# DA2_SCH_PAGE1.net
KiCad netlist of a schematic drawn in Altium Designer
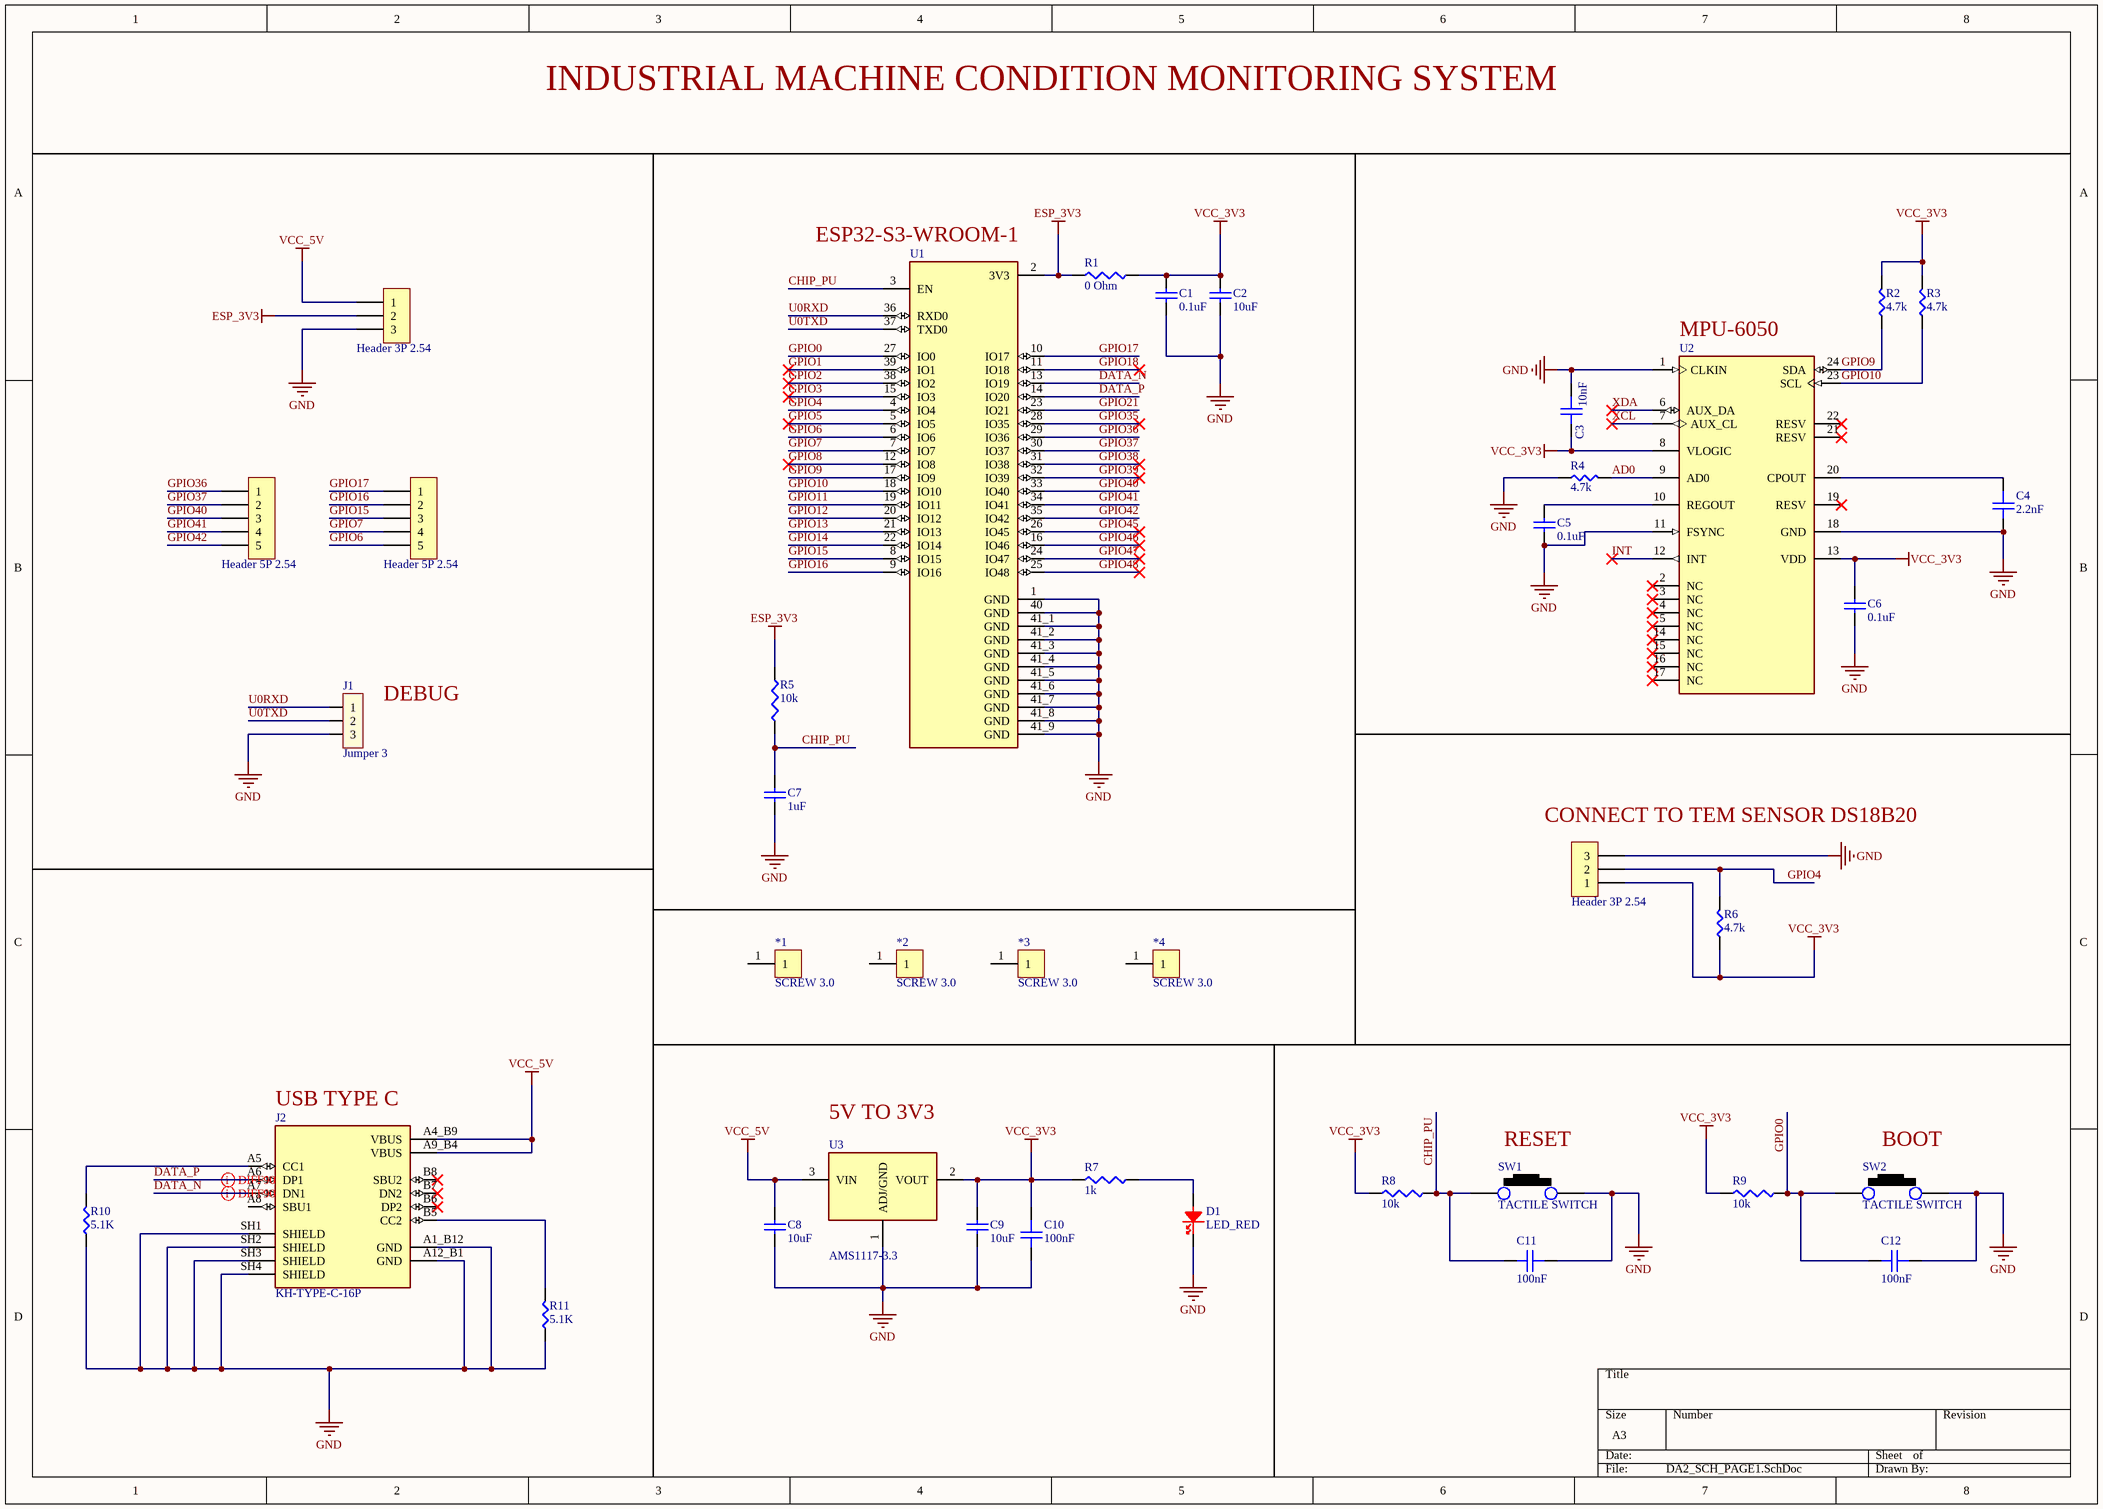
[diagram p0: DA2_SCH_PAGE1.SchDoc]

(export (version "E")
  (design (tool "Eeschema 10.0.6"))
  (components
    (comp (ref "*1")
      (value "SCREW 3.0")
      (footprint "Screw 3.0 v2")
      (libsource (lib "DA2") (part "SCREW 3.0"))
    )
    (comp (ref "*2")
      (value "SCREW 3.0")
      (footprint "Screw 3.0 v2")
      (libsource (lib "DA2") (part "SCREW 3.0"))
    )
    (comp (ref "*3")
      (value "SCREW 3.0")
      (footprint "Screw 3.0 v2")
      (libsource (lib "DA2") (part "SCREW 3.0"))
    )
    (comp (ref "*4")
      (value "SCREW 3.0")
      (footprint "Screw 3.0 v2")
      (libsource (lib "DA2") (part "SCREW 3.0"))
    )
    (comp (ref "C1")
      (value "0.1uF")
      (footprint "Tu 0805")
      (description "Dán 0805")
      (fields
        (field (name "MANUFACTURER") "Samsung Electro-Mechanics")
        (field (name "MANUFACTURER PART NUMBER") "CL05B104KB5NNWC")
      )
      (libsource (lib "DA2") (part "Tu 0.1uF"))
    )
    (comp (ref "C2")
      (value "10uF")
      (footprint "Tu 0805")
      (description "Dán 0805")
      (fields
        (field (name "MANUFACTURER") "Samsung Electro-Mechanics")
        (field (name "MANUFACTURER PART NUMBER") "CL05A106MP5NUNC")
      )
      (libsource (lib "DA2") (part "Tu 10uF"))
    )
    (comp (ref "C3")
      (value "10nF")
      (footprint "tu 0805")
      (description "Dán 0805")
      (libsource (lib "DA2") (part "Tu 10nF"))
    )
    (comp (ref "C4")
      (value "2.2nF")
      (footprint "tu 0805")
      (description "Dán 0805")
      (libsource (lib "DA2") (part "Tu 2.2nF"))
    )
    (comp (ref "C5")
      (value "0.1uF")
      (footprint "Tu 0805")
      (description "Dán 0805")
      (fields
        (field (name "MANUFACTURER") "Samsung Electro-Mechanics")
        (field (name "MANUFACTURER PART NUMBER") "CL05B104KB5NNWC")
      )
      (libsource (lib "DA2") (part "Tu 0.1uF"))
    )
    (comp (ref "C6")
      (value "0.1uF")
      (footprint "Tu 0805")
      (description "Dán 0805")
      (fields
        (field (name "MANUFACTURER") "Samsung Electro-Mechanics")
        (field (name "MANUFACTURER PART NUMBER") "CL05B104KB5NNWC")
      )
      (libsource (lib "DA2") (part "Tu 0.1uF"))
    )
    (comp (ref "C7")
      (value "1uF")
      (footprint "Tu 0805")
      (description "Dán 0805")
      (fields
        (field (name "MANUFACTURER") "Murata")
        (field (name "MANUFACTURER PART NUMBER") "GRM155R6YA105KE11D")
      )
      (libsource (lib "DA2") (part "Tu 1uF"))
    )
    (comp (ref "C8")
      (value "10uF")
      (footprint "Tu 0805")
      (description "Dán 0805")
      (fields
        (field (name "MANUFACTURER") "Samsung Electro-Mechanics")
        (field (name "MANUFACTURER PART NUMBER") "CL05A106MP5NUNC")
      )
      (libsource (lib "DA2") (part "Tu 10uF"))
    )
    (comp (ref "C9")
      (value "10uF")
      (footprint "Tu 0805")
      (description "Dán 0805")
      (fields
        (field (name "MANUFACTURER") "Samsung Electro-Mechanics")
        (field (name "MANUFACTURER PART NUMBER") "CL05A106MP5NUNC")
      )
      (libsource (lib "DA2") (part "Tu 10uF"))
    )
    (comp (ref "C10")
      (value "100nF")
      (footprint "tu 0805")
      (description "Dán 0805")
      (libsource (lib "DA2") (part "Tu 100nF"))
    )
    (comp (ref "C11")
      (value "100nF")
      (footprint "tu 0805")
      (description "Dán 0805")
      (libsource (lib "DA2") (part "Tu 100nF"))
    )
    (comp (ref "C12")
      (value "100nF")
      (footprint "tu 0805")
      (description "Dán 0805")
      (libsource (lib "DA2") (part "Tu 100nF"))
    )
    (comp (ref "D1")
      (value "LED_RED")
      (footprint "LED 0805")
      (description "LED RED 0402 SMD")
      (fields
        (field (name "MANUFACTURER") "Vishay")
        (field (name "MANUFACTURER PART NUMBER") "VLMS1500-GS08")
      )
      (libsource (lib "DA2") (part "VLMS1500-GS08"))
    )
    (comp (ref "H1")
      (value "Header 3P 2.54")
      (footprint "XH2.54M-3")
      (description "Cắm")
      (libsource (lib "DA2") (part "Header 3P 2.54 Duc Thang"))
    )
    (comp (ref "H2")
      (value "Header 5P 2.54")
      (footprint "XH2.54M-5")
      (description "Cắm")
      (libsource (lib "DA2") (part "Header 5P 2.54 Duc Thang"))
    )
    (comp (ref "H3")
      (value "Header 5P 2.54")
      (footprint "XH2.54M-5")
      (description "Cắm")
      (libsource (lib "DA2") (part "Header 5P 2.54 Duc Thang"))
    )
    (comp (ref "H4")
      (value "Header 3P 2.54")
      (footprint "XH2.54M-3")
      (description "Cắm")
      (libsource (lib "") (part "Header 3P 2.54 Duc Thang_1"))
    )
    (comp (ref "J1") (value "Jumper 3") (footprint "JP3") (libsource (lib "lpson") (part "JP3")))
    (comp (ref "J2")
      (value "KH-TYPE-C-16P")
      (footprint "KINGHELM_KH-TYPE-C-16P")
      (fields (field (name "MF") "kinghelm"))
      (libsource (lib "DA2") (part "KH-TYPE-C-16P"))
    )
    (comp (ref "R1")
      (value "0 Ohm")
      (footprint "Tro SMD 0805")
      (description "Dán 0805")
      (fields
        (field (name "MANUFACTURER") "Yageo Group")
        (field (name "MANUFACTURER PART NUMBER") "RC0402JR-070RL")
      )
      (libsource (lib "DA2") (part "Tro 0Ohm"))
    )
    (comp (ref "R2")
      (value "4.7k")
      (footprint "tro smd 0805")
      (description "Dán 0805")
      (libsource (lib "DA2") (part "Tro 4.7k"))
    )
    (comp (ref "R3")
      (value "4.7k")
      (footprint "tro smd 0805")
      (description "Dán 0805")
      (libsource (lib "DA2") (part "Tro 4.7k"))
    )
    (comp (ref "R4")
      (value "4.7k")
      (footprint "tro smd 0805")
      (description "Dán 0805")
      (libsource (lib "DA2") (part "Tro 4.7k"))
    )
    (comp (ref "R5")
      (value "10k")
      (footprint "Tro SMD 0805")
      (description "Dán 0805")
      (fields
        (field (name "MANUFACTURER") "Yageo Group")
        (field (name "MANUFACTURER PART NUMBER") "RC0402FR-0710KL")
      )
      (libsource (lib "DA2") (part "Tro 10k"))
    )
    (comp (ref "R6")
      (value "4.7k")
      (footprint "tro smd 0805")
      (description "Dán 0805")
      (libsource (lib "DA2") (part "Tro 4.7k"))
    )
    (comp (ref "R7")
      (value "1k")
      (footprint "Tro SMD 0805")
      (description "Dán 0805")
      (fields
        (field (name "MANUFACTURER") "Yageo Group")
        (field (name "MANUFACTURER PART NUMBER") "RC0402JR-071KL")
      )
      (libsource (lib "DA2") (part "Tro 1k"))
    )
    (comp (ref "R8")
      (value "10k")
      (footprint "Tro SMD 0805")
      (description "Dán 0805")
      (fields
        (field (name "MANUFACTURER") "Yageo Group")
        (field (name "MANUFACTURER PART NUMBER") "RC0402FR-0710KL")
      )
      (libsource (lib "DA2") (part "Tro 10k"))
    )
    (comp (ref "R9")
      (value "10k")
      (footprint "Tro SMD 0805")
      (description "Dán 0805")
      (fields
        (field (name "MANUFACTURER") "Yageo Group")
        (field (name "MANUFACTURER PART NUMBER") "RC0402FR-0710KL")
      )
      (libsource (lib "DA2") (part "Tro 10k"))
    )
    (comp (ref "R10")
      (value "5.1K")
      (footprint "tro smd 0805")
      (description "Dán 0805")
      (libsource (lib "DA2") (part "Tro 5.1K"))
    )
    (comp (ref "R11")
      (value "5.1K")
      (footprint "tro smd 0805")
      (description "Dán 0805")
      (libsource (lib "DA2") (part "Tro 5.1K"))
    )
    (comp (ref "SW1")
      (value "TACTILE SWITCH")
      (footprint "SWITCH SMD")
      (description "Tactile Switch SPST-NO Top Actuated Surface Mount")
      (fields
        (field (name "MANUFACTURER") "ITT C&K")
        (field (name "MANUFACTURER PART NUMBER") "RS-282G05A3-SMRT")
      )
      (libsource (lib "DA2") (part "SW1_RS-282G05A3-SMRT-SMD"))
    )
    (comp (ref "SW2")
      (value "TACTILE SWITCH")
      (footprint "SWITCH SMD")
      (description "Tactile Switch SPST-NO Top Actuated Surface Mount")
      (fields
        (field (name "MANUFACTURER") "ITT C&K")
        (field (name "MANUFACTURER PART NUMBER") "RS-282G05A3-SMRT")
      )
      (libsource (lib "DA2") (part "SW1_RS-282G05A3-SMRT-SMD"))
    )
    (comp (ref "U1")
      (value "ESP32-S3-WROOM-1-N8R2")
      (footprint "XCVR_ESP32-S3-WROOM-1-N8R2")
      (description "WiFi 802.11a/b/g/n, Bluetooth v5.0 Transceiver Module 2.4GHz Antenna Not Included -")
      (fields (field (name "MF") "Espressif Systems"))
      (libsource (lib "Schlib1") (part "ESP32-S3-WROOM-1-N8R2"))
    )
    (comp (ref "U2")
      (value "MPU-6050")
      (footprint "QFN50P400X400X95-24N")
      (description "MPU-6050 series Accelerometer, Gyroscope, 3 Axis Sensor Evaluation Board")
      (fields (field (name "MF") "TDK InvenSense"))
      (libsource (lib "Schlib1") (part "MPU-6050"))
    )
    (comp (ref "U3")
      (value "AMS1117-3.3")
      (footprint "SOT229P700X180-4N")
      (description "Linear Voltage Regulator IC Positive Fixed 1 Output 1A SOT-223-3L")
      (fields (field (name "MF") "UMW"))
      (libsource (lib "Schlib1") (part "AMS1117-3.3"))
    )
  )
  (nets
    (net (code "1") (name "/AD0") (class "Default")
      (node (ref "R4") (pin "2") (pinfunction "2_2") (pintype "passive"))
      (node (ref "U2") (pin "9") (pinfunction "AD0_9") (pintype "passive"))
    )
    (net (code "2") (name "/CHIP_PU") (class "Default")
      (node (ref "C11") (pin "2") (pinfunction "2_2") (pintype "passive"))
      (node (ref "C7") (pin "2") (pinfunction "2_2") (pintype "passive"))
      (node (ref "R5") (pin "1") (pinfunction "1_1") (pintype "passive"))
      (node (ref "R8") (pin "2") (pinfunction "2_2") (pintype "passive"))
      (node (ref "SW1") (pin "1") (pinfunction "1_1") (pintype "passive"))
      (node (ref "U1") (pin "3") (pinfunction "EN_3") (pintype "passive"))
    )
    (net (code "3") (name "/DATA_N") (class "Default")
      (node (ref "J2") (pin "A7") (pinfunction "DN1_A7") (pintype "bidirectional"))
      (node (ref "U1") (pin "13") (pinfunction "IO19_13") (pintype "bidirectional"))
    )
    (net (code "4") (name "/DATA_P") (class "Default")
      (node (ref "J2") (pin "A6") (pinfunction "DP1_A6") (pintype "bidirectional"))
      (node (ref "U1") (pin "14") (pinfunction "IO20_14") (pintype "bidirectional"))
    )
    (net (code "5") (name "/GPIO0") (class "Default")
      (node (ref "C12") (pin "2") (pinfunction "2_2") (pintype "passive"))
      (node (ref "R9") (pin "2") (pinfunction "2_2") (pintype "passive"))
      (node (ref "SW2") (pin "1") (pinfunction "1_1") (pintype "passive"))
      (node (ref "U1") (pin "27") (pinfunction "IO0_27") (pintype "bidirectional"))
    )
    (net (code "6") (name "/GPIO1") (class "Default")
      (node (ref "U1") (pin "39") (pinfunction "IO1_39") (pintype "bidirectional+no_connect"))
    )
    (net (code "7") (name "/GPIO2") (class "Default")
      (node (ref "U1") (pin "38") (pinfunction "IO2_38") (pintype "bidirectional+no_connect"))
    )
    (net (code "8") (name "/GPIO3") (class "Default")
      (node (ref "U1") (pin "15") (pinfunction "IO3_15") (pintype "bidirectional+no_connect"))
    )
    (net (code "9") (name "/GPIO4") (class "Default")
      (node (ref "H4") (pin "2") (pinfunction "2_2") (pintype "passive"))
      (node (ref "R6") (pin "2") (pinfunction "2_2") (pintype "passive"))
      (node (ref "U1") (pin "4") (pinfunction "IO4_4") (pintype "bidirectional"))
    )
    (net (code "10") (name "/GPIO5") (class "Default")
      (node (ref "U1") (pin "5") (pinfunction "IO5_5") (pintype "bidirectional+no_connect"))
    )
    (net (code "11") (name "/GPIO6") (class "Default")
      (node (ref "H3") (pin "5") (pinfunction "5_5") (pintype "passive"))
      (node (ref "U1") (pin "6") (pinfunction "IO6_6") (pintype "bidirectional"))
    )
    (net (code "12") (name "/GPIO7") (class "Default")
      (node (ref "H3") (pin "4") (pinfunction "4_4") (pintype "passive"))
      (node (ref "U1") (pin "7") (pinfunction "IO7_7") (pintype "bidirectional"))
    )
    (net (code "13") (name "/GPIO8") (class "Default")
      (node (ref "U1") (pin "12") (pinfunction "IO8_12") (pintype "bidirectional+no_connect"))
    )
    (net (code "14") (name "/GPIO9") (class "Default")
      (node (ref "R2") (pin "1") (pinfunction "1_1") (pintype "passive"))
      (node (ref "U1") (pin "17") (pinfunction "IO9_17") (pintype "bidirectional"))
      (node (ref "U2") (pin "24") (pinfunction "SDA_24") (pintype "bidirectional"))
    )
    (net (code "15") (name "/GPIO10") (class "Default")
      (node (ref "R3") (pin "1") (pinfunction "1_1") (pintype "passive"))
      (node (ref "U1") (pin "18") (pinfunction "IO10_18") (pintype "bidirectional"))
      (node (ref "U2") (pin "23") (pinfunction "SCL_23") (pintype "input"))
    )
    (net (code "16") (name "/GPIO11") (class "Default")
      (node (ref "U1") (pin "19") (pinfunction "IO11_19") (pintype "bidirectional"))
    )
    (net (code "17") (name "/GPIO12") (class "Default")
      (node (ref "U1") (pin "20") (pinfunction "IO12_20") (pintype "bidirectional"))
    )
    (net (code "18") (name "/GPIO13") (class "Default")
      (node (ref "U1") (pin "21") (pinfunction "IO13_21") (pintype "bidirectional"))
    )
    (net (code "19") (name "/GPIO14") (class "Default")
      (node (ref "U1") (pin "22") (pinfunction "IO14_22") (pintype "bidirectional"))
    )
    (net (code "20") (name "/GPIO15") (class "Default")
      (node (ref "H3") (pin "3") (pinfunction "3_3") (pintype "passive"))
      (node (ref "U1") (pin "8") (pinfunction "IO15_8") (pintype "bidirectional"))
    )
    (net (code "21") (name "/GPIO16") (class "Default")
      (node (ref "H3") (pin "2") (pinfunction "2_2") (pintype "passive"))
      (node (ref "U1") (pin "9") (pinfunction "IO16_9") (pintype "bidirectional"))
    )
    (net (code "22") (name "/GPIO17") (class "Default")
      (node (ref "H3") (pin "1") (pinfunction "1_1") (pintype "passive"))
      (node (ref "U1") (pin "10") (pinfunction "IO17_10") (pintype "bidirectional"))
    )
    (net (code "23") (name "/GPIO18") (class "Default")
      (node (ref "U1") (pin "11") (pinfunction "IO18_11") (pintype "bidirectional+no_connect"))
    )
    (net (code "24") (name "/GPIO21") (class "Default")
      (node (ref "U1") (pin "23") (pinfunction "IO21_23") (pintype "bidirectional"))
    )
    (net (code "25") (name "/GPIO35") (class "Default")
      (node (ref "U1") (pin "28") (pinfunction "IO35_28") (pintype "bidirectional+no_connect"))
    )
    (net (code "26") (name "/GPIO36") (class "Default")
      (node (ref "H2") (pin "1") (pinfunction "1_1") (pintype "passive"))
      (node (ref "U1") (pin "29") (pinfunction "IO36_29") (pintype "bidirectional"))
    )
    (net (code "27") (name "/GPIO37") (class "Default")
      (node (ref "H2") (pin "2") (pinfunction "2_2") (pintype "passive"))
      (node (ref "U1") (pin "30") (pinfunction "IO37_30") (pintype "bidirectional"))
    )
    (net (code "28") (name "/GPIO38") (class "Default")
      (node (ref "U1") (pin "31") (pinfunction "IO38_31") (pintype "bidirectional+no_connect"))
    )
    (net (code "29") (name "/GPIO39") (class "Default")
      (node (ref "U1") (pin "32") (pinfunction "IO39_32") (pintype "bidirectional+no_connect"))
    )
    (net (code "30") (name "/GPIO40") (class "Default")
      (node (ref "H2") (pin "3") (pinfunction "3_3") (pintype "passive"))
      (node (ref "U1") (pin "33") (pinfunction "IO40_33") (pintype "bidirectional"))
    )
    (net (code "31") (name "/GPIO41") (class "Default")
      (node (ref "H2") (pin "4") (pinfunction "4_4") (pintype "passive"))
      (node (ref "U1") (pin "34") (pinfunction "IO41_34") (pintype "bidirectional"))
    )
    (net (code "32") (name "/GPIO42") (class "Default")
      (node (ref "H2") (pin "5") (pinfunction "5_5") (pintype "passive"))
      (node (ref "U1") (pin "35") (pinfunction "IO42_35") (pintype "bidirectional"))
    )
    (net (code "33") (name "/GPIO45") (class "Default")
      (node (ref "U1") (pin "26") (pinfunction "IO45_26") (pintype "bidirectional+no_connect"))
    )
    (net (code "34") (name "/GPIO46") (class "Default")
      (node (ref "U1") (pin "16") (pinfunction "IO46_16") (pintype "bidirectional+no_connect"))
    )
    (net (code "35") (name "/GPIO47") (class "Default")
      (node (ref "U1") (pin "24") (pinfunction "IO47_24") (pintype "bidirectional+no_connect"))
    )
    (net (code "36") (name "/GPIO48") (class "Default")
      (node (ref "U1") (pin "25") (pinfunction "IO48_25") (pintype "bidirectional+no_connect"))
    )
    (net (code "37") (name "/INT") (class "Default")
      (node (ref "U2") (pin "12") (pinfunction "INT_12") (pintype "output+no_connect"))
    )
    (net (code "38") (name "/U0RXD") (class "Default")
      (node (ref "J1") (pin "1") (pinfunction "1_1") (pintype "passive"))
      (node (ref "U1") (pin "36") (pinfunction "RXD0_36") (pintype "bidirectional"))
    )
    (net (code "39") (name "/U0TXD") (class "Default")
      (node (ref "J1") (pin "2") (pinfunction "2_2") (pintype "passive"))
      (node (ref "U1") (pin "37") (pinfunction "TXD0_37") (pintype "bidirectional"))
    )
    (net (code "40") (name "/XCL") (class "Default")
      (node (ref "U2") (pin "7") (pinfunction "AUX_CL_7") (pintype "output+no_connect"))
    )
    (net (code "41") (name "/XDA") (class "Default")
      (node (ref "U2") (pin "6") (pinfunction "AUX_DA_6") (pintype "bidirectional+no_connect"))
    )
    (net (code "42") (name "ESP_3V3") (class "Default")
      (node (ref "H1") (pin "2") (pinfunction "2_2") (pintype "passive"))
      (node (ref "R1") (pin "1") (pinfunction "1_1") (pintype "passive"))
      (node (ref "R5") (pin "2") (pinfunction "2_2") (pintype "passive"))
      (node (ref "U1") (pin "2") (pinfunction "3V3_2") (pintype "power_in"))
    )
    (net (code "43") (name "GND") (class "Default")
      (node (ref "C1") (pin "1") (pinfunction "1_1") (pintype "passive"))
      (node (ref "C10") (pin "2") (pinfunction "2_2") (pintype "passive"))
      (node (ref "C11") (pin "1") (pinfunction "1_1") (pintype "passive"))
      (node (ref "C12") (pin "1") (pinfunction "1_1") (pintype "passive"))
      (node (ref "C2") (pin "1") (pinfunction "1_1") (pintype "passive"))
      (node (ref "C3") (pin "1") (pinfunction "1_1") (pintype "passive"))
      (node (ref "C4") (pin "2") (pinfunction "2_2") (pintype "passive"))
      (node (ref "C5") (pin "1") (pinfunction "1_1") (pintype "passive"))
      (node (ref "C6") (pin "1") (pinfunction "1_1") (pintype "passive"))
      (node (ref "C7") (pin "1") (pinfunction "1_1") (pintype "passive"))
      (node (ref "C8") (pin "1") (pinfunction "1_1") (pintype "passive"))
      (node (ref "C9") (pin "1") (pinfunction "1_1") (pintype "passive"))
      (node (ref "D1") (pin "1") (pinfunction "1_1") (pintype "passive"))
      (node (ref "H1") (pin "3") (pinfunction "3_3") (pintype "passive"))
      (node (ref "H4") (pin "3") (pinfunction "3_3") (pintype "passive"))
      (node (ref "J1") (pin "3") (pinfunction "3_3") (pintype "passive"))
      (node (ref "J2") (pin "A12_B1") (pinfunction "GND_A12_B1") (pintype "power_in"))
      (node (ref "J2") (pin "A1_B12") (pinfunction "GND_A1_B12") (pintype "power_in"))
      (node (ref "J2") (pin "SH1") (pinfunction "SHIELD_SH1") (pintype "passive"))
      (node (ref "J2") (pin "SH2") (pinfunction "SHIELD_SH2") (pintype "passive"))
      (node (ref "J2") (pin "SH3") (pinfunction "SHIELD_SH3") (pintype "passive"))
      (node (ref "J2") (pin "SH4") (pinfunction "SHIELD_SH4") (pintype "passive"))
      (node (ref "R10") (pin "1") (pinfunction "1_1") (pintype "passive"))
      (node (ref "R11") (pin "1") (pinfunction "1_1") (pintype "passive"))
      (node (ref "R4") (pin "1") (pinfunction "1_1") (pintype "passive"))
      (node (ref "SW1") (pin "2") (pinfunction "2_2") (pintype "passive"))
      (node (ref "SW2") (pin "2") (pinfunction "2_2") (pintype "passive"))
      (node (ref "U1") (pin "1") (pinfunction "GND_1") (pintype "power_in"))
      (node (ref "U1") (pin "40") (pinfunction "GND_40") (pintype "power_in"))
      (node (ref "U1") (pin "41_1") (pinfunction "GND_41_1") (pintype "power_in"))
      (node (ref "U1") (pin "41_2") (pinfunction "GND_41_2") (pintype "power_in"))
      (node (ref "U1") (pin "41_3") (pinfunction "GND_41_3") (pintype "power_in"))
      (node (ref "U1") (pin "41_4") (pinfunction "GND_41_4") (pintype "power_in"))
      (node (ref "U1") (pin "41_5") (pinfunction "GND_41_5") (pintype "power_in"))
      (node (ref "U1") (pin "41_6") (pinfunction "GND_41_6") (pintype "power_in"))
      (node (ref "U1") (pin "41_7") (pinfunction "GND_41_7") (pintype "power_in"))
      (node (ref "U1") (pin "41_8") (pinfunction "GND_41_8") (pintype "power_in"))
      (node (ref "U1") (pin "41_9") (pinfunction "GND_41_9") (pintype "power_in"))
      (node (ref "U2") (pin "1") (pinfunction "CLKIN_1") (pintype "input"))
      (node (ref "U2") (pin "11") (pinfunction "FSYNC_11") (pintype "input"))
      (node (ref "U2") (pin "18") (pinfunction "GND_18") (pintype "power_in"))
      (node (ref "U3") (pin "1") (pinfunction "ADJ/GND_1") (pintype "power_in"))
    )
    (net (code "44") (name "Net-(D1-Pad2)") (class "Default")
      (node (ref "D1") (pin "2") (pinfunction "2_2") (pintype "passive"))
      (node (ref "R7") (pin "2") (pinfunction "2_2") (pintype "passive"))
    )
    (net (code "45") (name "Net-(J2-CC1)") (class "Default")
      (node (ref "J2") (pin "A5") (pinfunction "CC1_A5") (pintype "bidirectional"))
      (node (ref "R10") (pin "2") (pinfunction "2_2") (pintype "passive"))
    )
    (net (code "46") (name "Net-(J2-CC2)") (class "Default")
      (node (ref "J2") (pin "B5") (pinfunction "CC2_B5") (pintype "bidirectional"))
      (node (ref "R11") (pin "2") (pinfunction "2_2") (pintype "passive"))
    )
    (net (code "47") (name "Net-(U2-CPOUT)") (class "Default")
      (node (ref "C4") (pin "1") (pinfunction "1_1") (pintype "passive"))
      (node (ref "U2") (pin "20") (pinfunction "CPOUT_20") (pintype "passive"))
    )
    (net (code "48") (name "Net-(U2-REGOUT)") (class "Default")
      (node (ref "C5") (pin "2") (pinfunction "2_2") (pintype "passive"))
      (node (ref "U2") (pin "10") (pinfunction "REGOUT_10") (pintype "passive"))
    )
    (net (code "49") (name "VCC_3V3") (class "Default")
      (node (ref "C1") (pin "2") (pinfunction "2_2") (pintype "passive"))
      (node (ref "C10") (pin "1") (pinfunction "1_1") (pintype "passive"))
      (node (ref "C2") (pin "2") (pinfunction "2_2") (pintype "passive"))
      (node (ref "C3") (pin "2") (pinfunction "2_2") (pintype "passive"))
      (node (ref "C6") (pin "2") (pinfunction "2_2") (pintype "passive"))
      (node (ref "C9") (pin "2") (pinfunction "2_2") (pintype "passive"))
      (node (ref "H4") (pin "1") (pinfunction "1_1") (pintype "passive"))
      (node (ref "R1") (pin "2") (pinfunction "2_2") (pintype "passive"))
      (node (ref "R2") (pin "2") (pinfunction "2_2") (pintype "passive"))
      (node (ref "R3") (pin "2") (pinfunction "2_2") (pintype "passive"))
      (node (ref "R6") (pin "1") (pinfunction "1_1") (pintype "passive"))
      (node (ref "R7") (pin "1") (pinfunction "1_1") (pintype "passive"))
      (node (ref "R8") (pin "1") (pinfunction "1_1") (pintype "passive"))
      (node (ref "R9") (pin "1") (pinfunction "1_1") (pintype "passive"))
      (node (ref "U2") (pin "13") (pinfunction "VDD_13") (pintype "power_in"))
      (node (ref "U2") (pin "8") (pinfunction "VLOGIC_8") (pintype "power_in"))
      (node (ref "U3") (pin "2") (pinfunction "VOUT_2") (pintype "passive"))
    )
    (net (code "50") (name "VCC_5V") (class "Default")
      (node (ref "C8") (pin "2") (pinfunction "2_2") (pintype "passive"))
      (node (ref "H1") (pin "1") (pinfunction "1_1") (pintype "passive"))
      (node (ref "J2") (pin "A4_B9") (pinfunction "VBUS_A4_B9") (pintype "power_in"))
      (node (ref "J2") (pin "A9_B4") (pinfunction "VBUS_A9_B4") (pintype "power_in"))
      (node (ref "U3") (pin "3") (pinfunction "VIN_3") (pintype "passive"))
    )
    (net (code "51") (name "unconnected-(*1-Pad1)") (class "Default")
      (node (ref "*1") (pin "1") (pinfunction "1_1") (pintype "passive"))
    )
    (net (code "52") (name "unconnected-(*2-Pad1)") (class "Default")
      (node (ref "*2") (pin "1") (pinfunction "1_1") (pintype "passive"))
    )
    (net (code "53") (name "unconnected-(*3-Pad1)") (class "Default")
      (node (ref "*3") (pin "1") (pinfunction "1_1") (pintype "passive"))
    )
    (net (code "54") (name "unconnected-(*4-Pad1)") (class "Default")
      (node (ref "*4") (pin "1") (pinfunction "1_1") (pintype "passive"))
    )
    (net (code "55") (name "unconnected-(J2-DN2-PadB7)") (class "Default")
      (node (ref "J2") (pin "B7") (pinfunction "DN2_B7") (pintype "bidirectional+no_connect"))
    )
    (net (code "56") (name "unconnected-(J2-DP2-PadB6)") (class "Default")
      (node (ref "J2") (pin "B6") (pinfunction "DP2_B6") (pintype "bidirectional+no_connect"))
    )
    (net (code "57") (name "unconnected-(J2-SBU1-PadA8)") (class "Default")
      (node (ref "J2") (pin "A8") (pinfunction "SBU1_A8") (pintype "bidirectional"))
    )
    (net (code "58") (name "unconnected-(J2-SBU2-PadB8)") (class "Default")
      (node (ref "J2") (pin "B8") (pinfunction "SBU2_B8") (pintype "bidirectional+no_connect"))
    )
    (net (code "59") (name "unconnected-(U2-NC-Pad2)") (class "Default")
      (node (ref "U2") (pin "2") (pinfunction "NC_2") (pintype "passive+no_connect"))
    )
    (net (code "60") (name "unconnected-(U2-NC-Pad3)") (class "Default")
      (node (ref "U2") (pin "3") (pinfunction "NC_3") (pintype "passive+no_connect"))
    )
    (net (code "61") (name "unconnected-(U2-NC-Pad4)") (class "Default")
      (node (ref "U2") (pin "4") (pinfunction "NC_4") (pintype "passive+no_connect"))
    )
    (net (code "62") (name "unconnected-(U2-NC-Pad5)") (class "Default")
      (node (ref "U2") (pin "5") (pinfunction "NC_5") (pintype "passive+no_connect"))
    )
    (net (code "63") (name "unconnected-(U2-NC-Pad14)") (class "Default")
      (node (ref "U2") (pin "14") (pinfunction "NC_14") (pintype "passive+no_connect"))
    )
    (net (code "64") (name "unconnected-(U2-NC-Pad15)") (class "Default")
      (node (ref "U2") (pin "15") (pinfunction "NC_15") (pintype "passive+no_connect"))
    )
    (net (code "65") (name "unconnected-(U2-NC-Pad16)") (class "Default")
      (node (ref "U2") (pin "16") (pinfunction "NC_16") (pintype "passive+no_connect"))
    )
    (net (code "66") (name "unconnected-(U2-NC-Pad17)") (class "Default")
      (node (ref "U2") (pin "17") (pinfunction "NC_17") (pintype "passive+no_connect"))
    )
    (net (code "67") (name "unconnected-(U2-RESV-Pad19)") (class "Default")
      (node (ref "U2") (pin "19") (pinfunction "RESV_19") (pintype "passive+no_connect"))
    )
    (net (code "68") (name "unconnected-(U2-RESV-Pad21)") (class "Default")
      (node (ref "U2") (pin "21") (pinfunction "RESV_21") (pintype "passive+no_connect"))
    )
    (net (code "69") (name "unconnected-(U2-RESV-Pad22)") (class "Default")
      (node (ref "U2") (pin "22") (pinfunction "RESV_22") (pintype "passive+no_connect"))
    )
  )
)
